# RL78.net
KiCad netlist of a schematic drawn in Altium Designer
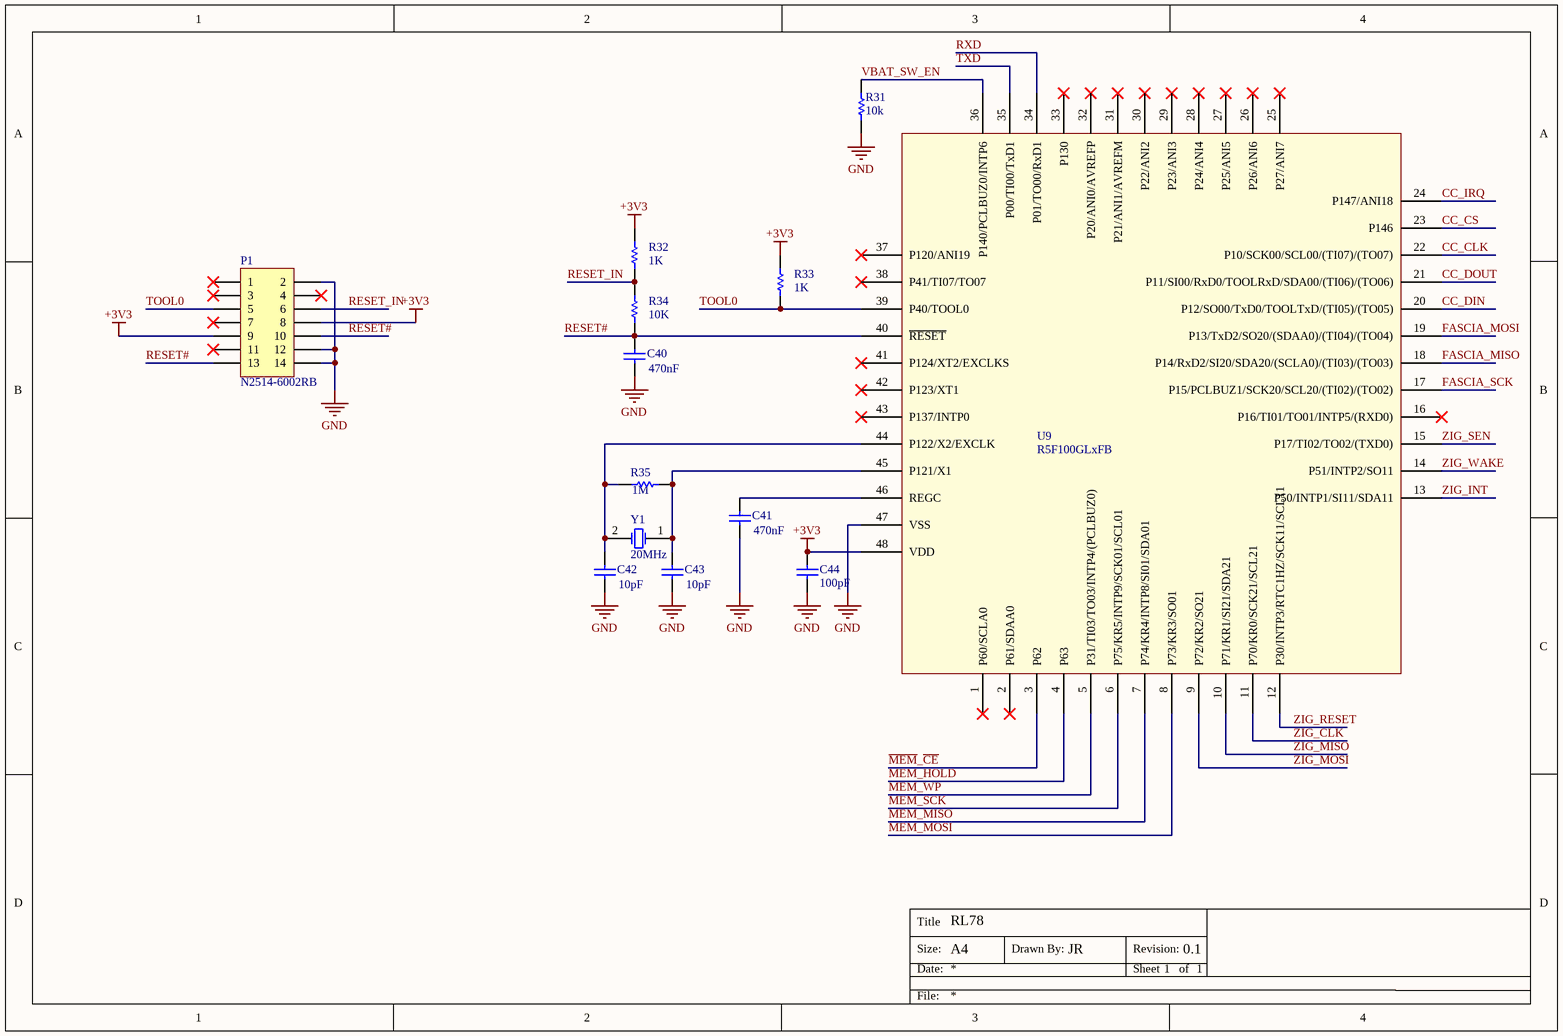
[diagram p0: RL78.SchDoc]

(export (version "E")
  (design (tool "Eeschema 10.0.6"))
  (components
    (comp (ref "C40")
      (value "470nF")
      (footprint "CAPC1005L")
      (description "Capacitor")
      (fields (field (name "Comment") "Cap") (field (name "PUBLISHER") "Altium Limited"))
      (libsource (lib "Miscellaneous Devices") (part "Cap"))
    )
    (comp (ref "C41")
      (value "470nF")
      (footprint "CAPC1005L")
      (description "Capacitor")
      (fields (field (name "Comment") "Cap") (field (name "PUBLISHER") "Altium Limited"))
      (libsource (lib "Miscellaneous Devices") (part "Cap"))
    )
    (comp (ref "C42")
      (value "10pF")
      (footprint "CAPC1005L")
      (description "Capacitor")
      (fields (field (name "Comment") "Cap") (field (name "PUBLISHER") "Altium Limited"))
      (libsource (lib "Miscellaneous Devices") (part "Cap"))
    )
    (comp (ref "C43")
      (value "10pF")
      (footprint "CAPC1005L")
      (description "Capacitor")
      (fields (field (name "Comment") "Cap") (field (name "PUBLISHER") "Altium Limited"))
      (libsource (lib "Miscellaneous Devices") (part "Cap"))
    )
    (comp (ref "C44")
      (value "100pF")
      (footprint "CAPC1005L")
      (description "Capacitor")
      (fields (field (name "Comment") "Cap") (field (name "PUBLISHER") "Altium Limited"))
      (libsource (lib "Miscellaneous Devices") (part "Cap"))
    )
    (comp (ref "P1")
      (value "N2514-6002RB")
      (footprint "N2514-6002RB")
      (description "Header, 7-Pin, Dual row N2514-6002RB")
      (fields (field (name "PUBLISHER") "Altium Limited"))
      (libsource (lib "Miscellaneous Connectors") (part "Header 7X2"))
    )
    (comp (ref "R31")
      (value "10k")
      (footprint "RESC1005L")
      (description "Resistor, 68kOhm, 1/10W, 5%, 0603")
      (fields (field (name "MANUFACTURER") "Yageo") (field (name "Comment") "RC0603JR-0768KL"))
      (libsource (lib "Miscellaneous Devices") (part "Res Semi"))
    )
    (comp (ref "R32")
      (value "1K")
      (footprint "RESC1608L")
      (description "Resistor")
      (fields (field (name "Comment") "Res1") (field (name "PUBLISHER") "Altium Limited"))
      (libsource (lib "Miscellaneous Devices") (part "Res1"))
    )
    (comp (ref "R33")
      (value "1K")
      (footprint "RESC1005L")
      (description "Resistor")
      (fields (field (name "Comment") "Res1") (field (name "PUBLISHER") "Altium Limited"))
      (libsource (lib "Miscellaneous Devices") (part "Res1"))
    )
    (comp (ref "R34")
      (value "10K")
      (footprint "RESC1608L")
      (description "Resistor")
      (fields (field (name "Comment") "Res1") (field (name "PUBLISHER") "Altium Limited"))
      (libsource (lib "Miscellaneous Devices") (part "Res1"))
    )
    (comp (ref "R35")
      (value "1M")
      (footprint "RESC1005L")
      (description "Resistor")
      (fields (field (name "Comment") "Res1") (field (name "PUBLISHER") "Altium Limited"))
      (libsource (lib "Miscellaneous Devices") (part "Res1"))
    )
    (comp (ref "U9")
      (value "R5F100GLxFB")
      (footprint "R5F100GLxFB")
      (libsource (lib "wifiModule") (part "R5F100GLxFB"))
    )
    (comp (ref "Y1")
      (value "20MHz")
      (footprint "32Mhz Crystal")
      (description "Crystal Oscillator")
      (fields (field (name "PUBLISHER") "Altium Limited"))
      (libsource (lib "Miscellaneous Devices") (part "XTAL"))
    )
  )
  (nets
    (net (code "1") (name "+3V3") (class "Default")
      (node (ref "C44") (pin "2") (pinfunction "2_2") (pintype "passive"))
      (node (ref "P1") (pin "8") (pinfunction "8_8") (pintype "passive"))
      (node (ref "P1") (pin "9") (pinfunction "9_9") (pintype "passive"))
      (node (ref "R32") (pin "2") (pinfunction "2_2") (pintype "passive"))
      (node (ref "R33") (pin "2") (pinfunction "2_2") (pintype "passive"))
      (node (ref "U9") (pin "48") (pinfunction "VDD_48") (pintype "passive"))
    )
    (net (code "2") (name "/CC_CLK") (class "Default")
      (node (ref "U9") (pin "22") (pinfunction "P10/SCK00/SCL00/(TI07)/(TO07)_22") (pintype "passive"))
    )
    (net (code "3") (name "/CC_CS") (class "Default")
      (node (ref "U9") (pin "23") (pinfunction "P146_23") (pintype "passive"))
    )
    (net (code "4") (name "/CC_DIN") (class "Default")
      (node (ref "U9") (pin "20") (pinfunction "P12/SO00/TxD0/TOOLTxD/(TI05)/(TO05)_20") (pintype "passive"))
    )
    (net (code "5") (name "/CC_DOUT") (class "Default")
      (node (ref "U9") (pin "21") (pinfunction "P11/SI00/RxD0/TOOLRxD/SDA00/(TI06)/(TO06)_21") (pintype "passive"))
    )
    (net (code "6") (name "/CC_IRQ") (class "Default")
      (node (ref "U9") (pin "24") (pinfunction "P147/ANI18_24") (pintype "passive"))
    )
    (net (code "7") (name "/FASCIA_MISO") (class "Default")
      (node (ref "U9") (pin "18") (pinfunction "P14/RxD2/SI20/SDA20/(SCLA0)/(TI03)/(TO03)_18") (pintype "passive"))
    )
    (net (code "8") (name "/FASCIA_MOSI") (class "Default")
      (node (ref "U9") (pin "19") (pinfunction "P13/TxD2/SO20/(SDAA0)/(TI04)/(TO04)_19") (pintype "passive"))
    )
    (net (code "9") (name "/FASCIA_SCK") (class "Default")
      (node (ref "U9") (pin "17") (pinfunction "P15/PCLBUZ1/SCK20/SCL20/(TI02)/(TO02)_17") (pintype "passive"))
    )
    (net (code "10") (name "/MEM_MISO") (class "Default")
      (node (ref "U9") (pin "7") (pinfunction "P74/KR4/INTP8/SI01/SDA01_7") (pintype "passive"))
    )
    (net (code "11") (name "/MEM_MOSI") (class "Default")
      (node (ref "U9") (pin "8") (pinfunction "P73/KR3/SO01_8") (pintype "passive"))
    )
    (net (code "12") (name "/MEM_SCK") (class "Default")
      (node (ref "U9") (pin "6") (pinfunction "P75/KR5/INTP9/SCK01/SCL01_6") (pintype "passive"))
    )
    (net (code "13") (name "/RESET#") (class "Default")
      (node (ref "C40") (pin "2") (pinfunction "2_2") (pintype "passive"))
      (node (ref "P1") (pin "10") (pinfunction "10_10") (pintype "passive"))
      (node (ref "P1") (pin "13") (pinfunction "13_13") (pintype "passive"))
      (node (ref "R34") (pin "1") (pinfunction "1_1") (pintype "passive"))
      (node (ref "U9") (pin "40") (pinfunction "~{RESET}_40") (pintype "passive"))
    )
    (net (code "14") (name "/RESET_IN") (class "Default")
      (node (ref "P1") (pin "6") (pinfunction "6_6") (pintype "passive"))
      (node (ref "R32") (pin "1") (pinfunction "1_1") (pintype "passive"))
      (node (ref "R34") (pin "2") (pinfunction "2_2") (pintype "passive"))
    )
    (net (code "15") (name "/RXD") (class "Default")
      (node (ref "U9") (pin "34") (pinfunction "P01/TO00/RxD1_34") (pintype "passive"))
    )
    (net (code "16") (name "/TOOL0") (class "Default")
      (node (ref "P1") (pin "5") (pinfunction "5_5") (pintype "passive"))
      (node (ref "R33") (pin "1") (pinfunction "1_1") (pintype "passive"))
      (node (ref "U9") (pin "39") (pinfunction "P40/TOOL0_39") (pintype "passive"))
    )
    (net (code "17") (name "/TXD") (class "Default")
      (node (ref "U9") (pin "35") (pinfunction "P00/TI00/TxD1_35") (pintype "passive"))
    )
    (net (code "18") (name "/VBAT_SW_EN") (class "Default")
      (node (ref "R31") (pin "1") (pinfunction "1_1") (pintype "passive"))
      (node (ref "U9") (pin "36") (pinfunction "P140/PCLBUZ0/INTP6_36") (pintype "passive"))
    )
    (net (code "19") (name "/ZIG_CLK") (class "Default")
      (node (ref "U9") (pin "11") (pinfunction "P70/KR0/SCK21/SCL21_11") (pintype "passive"))
    )
    (net (code "20") (name "/ZIG_INT") (class "Default")
      (node (ref "U9") (pin "13") (pinfunction "P50/INTP1/SI11/SDA11_13") (pintype "passive"))
    )
    (net (code "21") (name "/ZIG_MISO") (class "Default")
      (node (ref "U9") (pin "10") (pinfunction "P71/KR1/SI21/SDA21_10") (pintype "passive"))
    )
    (net (code "22") (name "/ZIG_MOSI") (class "Default")
      (node (ref "U9") (pin "9") (pinfunction "P72/KR2/SO21_9") (pintype "passive"))
    )
    (net (code "23") (name "/ZIG_RESET") (class "Default")
      (node (ref "U9") (pin "12") (pinfunction "P30/INTP3/RTC1HZ/SCK11/SCL11_12") (pintype "passive"))
    )
    (net (code "24") (name "/ZIG_SEN") (class "Default")
      (node (ref "U9") (pin "15") (pinfunction "P17/TI02/TO02/(TXD0)_15") (pintype "passive"))
    )
    (net (code "25") (name "/ZIG_WAKE") (class "Default")
      (node (ref "U9") (pin "14") (pinfunction "P51/INTP2/SO11_14") (pintype "passive"))
    )
    (net (code "26") (name "/~{MEM}_~{CE}") (class "Default")
      (node (ref "U9") (pin "3") (pinfunction "P62_3") (pintype "passive"))
    )
    (net (code "27") (name "/~{MEM}_~{HOLD}") (class "Default")
      (node (ref "U9") (pin "4") (pinfunction "P63_4") (pintype "passive"))
    )
    (net (code "28") (name "/~{MEM}_~{WP}") (class "Default")
      (node (ref "U9") (pin "5") (pinfunction "P31/TI03/TO03/INTP4/(PCLBUZ0)_5") (pintype "passive"))
    )
    (net (code "29") (name "GND") (class "Default")
      (node (ref "C40") (pin "1") (pinfunction "1_1") (pintype "passive"))
      (node (ref "C41") (pin "1") (pinfunction "1_1") (pintype "passive"))
      (node (ref "C42") (pin "1") (pinfunction "1_1") (pintype "passive"))
      (node (ref "C43") (pin "1") (pinfunction "1_1") (pintype "passive"))
      (node (ref "C44") (pin "1") (pinfunction "1_1") (pintype "passive"))
      (node (ref "P1") (pin "12") (pinfunction "12_12") (pintype "passive"))
      (node (ref "P1") (pin "14") (pinfunction "14_14") (pintype "passive"))
      (node (ref "P1") (pin "2") (pinfunction "2_2") (pintype "passive"))
      (node (ref "R31") (pin "2") (pinfunction "2_2") (pintype "passive"))
      (node (ref "U9") (pin "47") (pinfunction "VSS_47") (pintype "passive"))
    )
    (net (code "30") (name "Net-(U9-P121{slash}X1)") (class "Default")
      (node (ref "C43") (pin "2") (pinfunction "2_2") (pintype "passive"))
      (node (ref "R35") (pin "1") (pinfunction "1_1") (pintype "passive"))
      (node (ref "U9") (pin "45") (pinfunction "P121/X1_45") (pintype "passive"))
      (node (ref "Y1") (pin "1") (pinfunction "OSC1_1") (pintype "passive"))
    )
    (net (code "31") (name "Net-(U9-P122{slash}X2{slash}EXCLK)") (class "Default")
      (node (ref "C42") (pin "2") (pinfunction "2_2") (pintype "passive"))
      (node (ref "R35") (pin "2") (pinfunction "2_2") (pintype "passive"))
      (node (ref "U9") (pin "44") (pinfunction "P122/X2/EXCLK_44") (pintype "passive"))
      (node (ref "Y1") (pin "2") (pinfunction "OSC2_2") (pintype "passive"))
    )
    (net (code "32") (name "Net-(U9-REGC)") (class "Default")
      (node (ref "C41") (pin "2") (pinfunction "2_2") (pintype "passive"))
      (node (ref "U9") (pin "46") (pinfunction "REGC_46") (pintype "passive"))
    )
    (net (code "33") (name "unconnected-(P1-Pad1)") (class "Default")
      (node (ref "P1") (pin "1") (pinfunction "1_1") (pintype "passive+no_connect"))
    )
    (net (code "34") (name "unconnected-(P1-Pad3)") (class "Default")
      (node (ref "P1") (pin "3") (pinfunction "3_3") (pintype "passive+no_connect"))
    )
    (net (code "35") (name "unconnected-(P1-Pad4)") (class "Default")
      (node (ref "P1") (pin "4") (pinfunction "4_4") (pintype "passive+no_connect"))
    )
    (net (code "36") (name "unconnected-(P1-Pad7)") (class "Default")
      (node (ref "P1") (pin "7") (pinfunction "7_7") (pintype "passive+no_connect"))
    )
    (net (code "37") (name "unconnected-(P1-Pad11)") (class "Default")
      (node (ref "P1") (pin "11") (pinfunction "11_11") (pintype "passive+no_connect"))
    )
    (net (code "38") (name "unconnected-(U9-P16{slash}TI01{slash}TO01{slash}INTP5{slash}(RXD0)-Pad16)") (class "Default")
      (node (ref "U9") (pin "16") (pinfunction "P16/TI01/TO01/INTP5/(RXD0)_16") (pintype "passive+no_connect"))
    )
    (net (code "39") (name "unconnected-(U9-P20{slash}ANI0{slash}AVREFP-Pad32)") (class "Default")
      (node (ref "U9") (pin "32") (pinfunction "P20/ANI0/AVREFP_32") (pintype "passive+no_connect"))
    )
    (net (code "40") (name "unconnected-(U9-P21{slash}ANI1{slash}AVREFM-Pad31)") (class "Default")
      (node (ref "U9") (pin "31") (pinfunction "P21/ANI1/AVREFM_31") (pintype "passive+no_connect"))
    )
    (net (code "41") (name "unconnected-(U9-P22{slash}ANI2-Pad30)") (class "Default")
      (node (ref "U9") (pin "30") (pinfunction "P22/ANI2_30") (pintype "passive+no_connect"))
    )
    (net (code "42") (name "unconnected-(U9-P23{slash}ANI3-Pad29)") (class "Default")
      (node (ref "U9") (pin "29") (pinfunction "P23/ANI3_29") (pintype "passive+no_connect"))
    )
    (net (code "43") (name "unconnected-(U9-P24{slash}ANI4-Pad28)") (class "Default")
      (node (ref "U9") (pin "28") (pinfunction "P24/ANI4_28") (pintype "passive+no_connect"))
    )
    (net (code "44") (name "unconnected-(U9-P25{slash}ANI5-Pad27)") (class "Default")
      (node (ref "U9") (pin "27") (pinfunction "P25/ANI5_27") (pintype "passive+no_connect"))
    )
    (net (code "45") (name "unconnected-(U9-P26{slash}ANI6-Pad26)") (class "Default")
      (node (ref "U9") (pin "26") (pinfunction "P26/ANI6_26") (pintype "passive+no_connect"))
    )
    (net (code "46") (name "unconnected-(U9-P27{slash}ANI7-Pad25)") (class "Default")
      (node (ref "U9") (pin "25") (pinfunction "P27/ANI7_25") (pintype "passive+no_connect"))
    )
    (net (code "47") (name "unconnected-(U9-P41{slash}TI07{slash}TO07-Pad38)") (class "Default")
      (node (ref "U9") (pin "38") (pinfunction "P41/TI07/TO07_38") (pintype "passive+no_connect"))
    )
    (net (code "48") (name "unconnected-(U9-P60{slash}SCLA0-Pad1)") (class "Default")
      (node (ref "U9") (pin "1") (pinfunction "P60/SCLA0_1") (pintype "passive+no_connect"))
    )
    (net (code "49") (name "unconnected-(U9-P61{slash}SDAA0-Pad2)") (class "Default")
      (node (ref "U9") (pin "2") (pinfunction "P61/SDAA0_2") (pintype "passive+no_connect"))
    )
    (net (code "50") (name "unconnected-(U9-P120{slash}ANI19-Pad37)") (class "Default")
      (node (ref "U9") (pin "37") (pinfunction "P120/ANI19_37") (pintype "passive+no_connect"))
    )
    (net (code "51") (name "unconnected-(U9-P123{slash}XT1-Pad42)") (class "Default")
      (node (ref "U9") (pin "42") (pinfunction "P123/XT1_42") (pintype "passive+no_connect"))
    )
    (net (code "52") (name "unconnected-(U9-P124{slash}XT2{slash}EXCLKS-Pad41)") (class "Default")
      (node (ref "U9") (pin "41") (pinfunction "P124/XT2/EXCLKS_41") (pintype "passive+no_connect"))
    )
    (net (code "53") (name "unconnected-(U9-P130-Pad33)") (class "Default")
      (node (ref "U9") (pin "33") (pinfunction "P130_33") (pintype "passive+no_connect"))
    )
    (net (code "54") (name "unconnected-(U9-P137{slash}INTP0-Pad43)") (class "Default")
      (node (ref "U9") (pin "43") (pinfunction "P137/INTP0_43") (pintype "passive+no_connect"))
    )
  )
)
